# BIRDS-5_FM__Z_Panel_Ver2.net
KiCad netlist of a schematic drawn in EAGLE
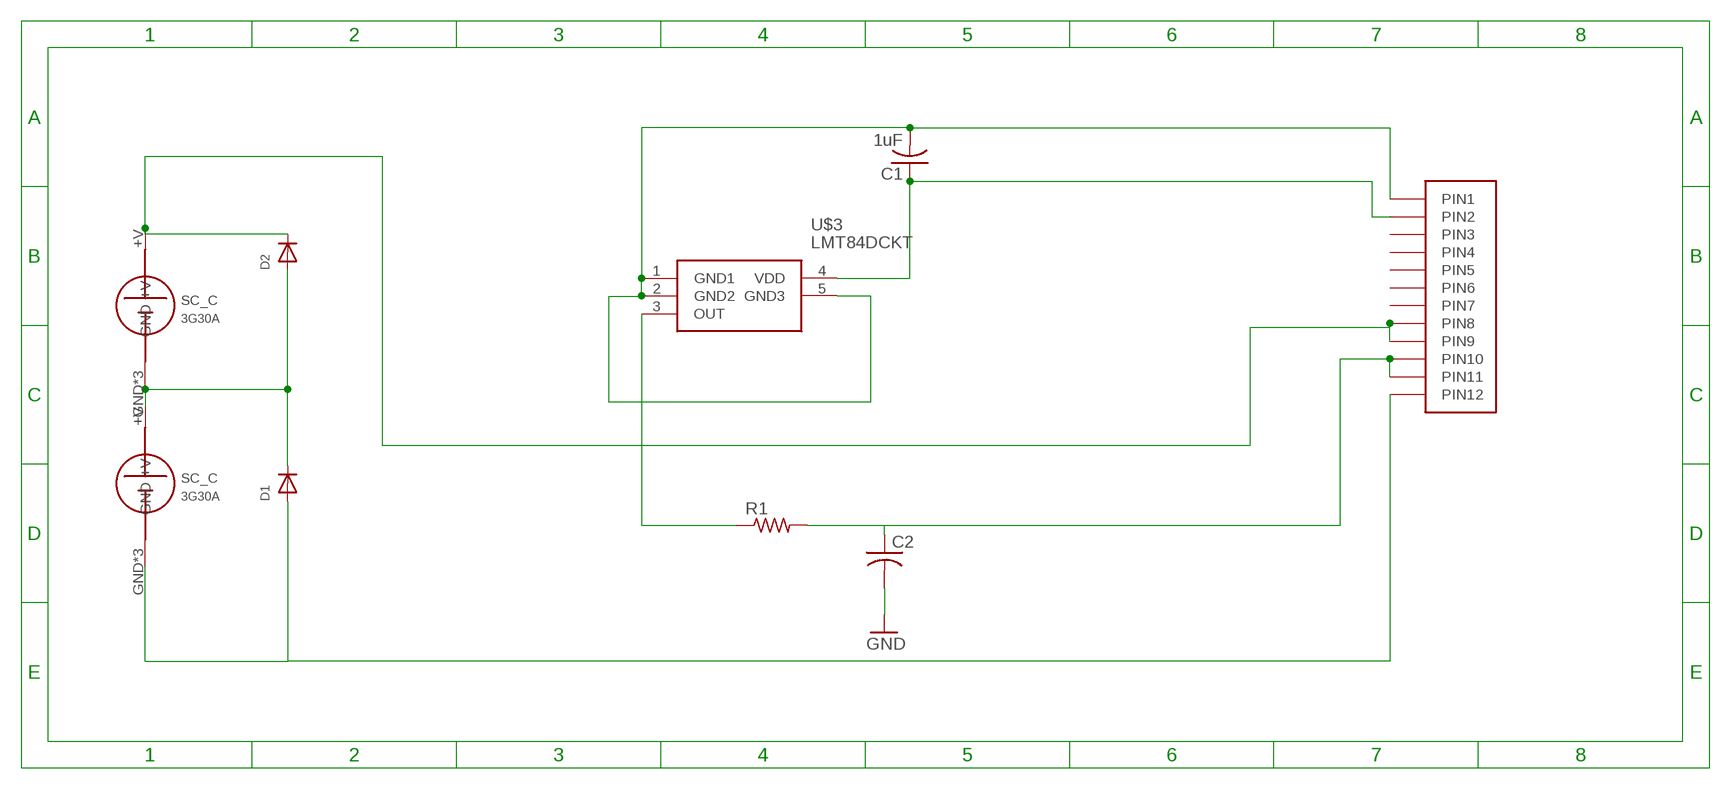
[diagram p0: schematic, sheet 1]

(export (version "E")
  (design (tool "Eeschema 10.0.6"))
  (components
    (comp (ref "C1")
      (value "1uF")
      (footprint "eagle-import:C2012")
      (libsource (lib "eagle-import") (part "C-USC2012"))
    )
    (comp (ref "C2")
      (value "C-USC2012")
      (footprint "eagle-import:C2012")
      (libsource (lib "eagle-import") (part "C-USC2012"))
    )
    (comp (ref "D1")
      (value "DIODE_SOD-123FL")
      (footprint "eagle-import:SOD-123FL")
      (libsource (lib "eagle-import") (part "DIODE_SOD-123FL"))
    )
    (comp (ref "D2")
      (value "DIODE_SOD-123FL")
      (footprint "eagle-import:SOD-123FL")
      (libsource (lib "eagle-import") (part "DIODE_SOD-123FL"))
    )
    (comp (ref "R1")
      (value "R-US_R0402")
      (footprint "eagle-import:R0402")
      (libsource (lib "eagle-import") (part "R-US_R0402"))
    )
    (comp (ref "U$1")
      (value "HEADER12PIN")
      (footprint "eagle-import:HEADER12PIN")
      (libsource (lib "eagle-import") (part "HEADER12PIN"))
    )
    (comp (ref "U$3")
      (value "LMT84DCKT")
      (footprint "eagle-import:SOT65P210X110-5N")
      (fields (field (name "RS_PART_NUMBER") "8115860"))
      (libsource (lib "eagle-import") (part "LMT84DCKT"))
    )
    (comp (ref "U$4")
      (value "SC_C")
      (footprint "eagle-import:SC_C")
      (libsource (lib "eagle-import") (part "SC_C"))
    )
    (comp (ref "U$5")
      (value "SC_C")
      (footprint "eagle-import:SC_C")
      (libsource (lib "eagle-import") (part "SC_C"))
    )
  )
  (nets
    (net (code "1") (name "GND") (class "Default")
      (node (ref "C1") (pin "2") (pinfunction "2_2") (pintype "passive"))
      (node (ref "C2") (pin "2") (pinfunction "2_2") (pintype "passive"))
      (node (ref "D1") (pin "A") (pinfunction "A_A") (pintype "passive"))
      (node (ref "U$1") (pin "P1") (pinfunction "PIN1_P1") (pintype "bidirectional"))
      (node (ref "U$1") (pin "P12") (pinfunction "PIN12_P12") (pintype "bidirectional"))
      (node (ref "U$3") (pin "1") (pinfunction "GND1_1") (pintype "power_in"))
      (node (ref "U$3") (pin "2") (pinfunction "GND2_2") (pintype "power_in"))
      (node (ref "U$3") (pin "5") (pinfunction "GND3_5") (pintype "power_in"))
      (node (ref "U$5") (pin "GND") (pinfunction "GND_GND") (pintype "bidirectional"))
      (node (ref "U$5") (pin "GND1") (pinfunction "GND_GND1") (pintype "bidirectional"))
      (node (ref "U$5") (pin "GND2") (pinfunction "GND_GND2") (pintype "bidirectional"))
    )
    (net (code "2") (name "Net-(D1-PadC)") (class "Default")
      (node (ref "D1") (pin "C") (pinfunction "C_C") (pintype "passive"))
      (node (ref "D2") (pin "A") (pinfunction "A_A") (pintype "passive"))
      (node (ref "U$4") (pin "GND") (pinfunction "GND_GND") (pintype "bidirectional"))
      (node (ref "U$4") (pin "GND1") (pinfunction "GND_GND1") (pintype "bidirectional"))
      (node (ref "U$4") (pin "GND2") (pinfunction "GND_GND2") (pintype "bidirectional"))
      (node (ref "U$5") (pin "+V") (pinfunction "+V_+V") (pintype "bidirectional"))
    )
    (net (code "3") (name "Net-(U$1-PIN2)") (class "Default")
      (node (ref "C1") (pin "1") (pinfunction "1_1") (pintype "passive"))
      (node (ref "U$1") (pin "P2") (pinfunction "PIN2_P2") (pintype "bidirectional"))
      (node (ref "U$3") (pin "4") (pinfunction "VDD_4") (pintype "power_in"))
    )
    (net (code "4") (name "Net-(U$1-PIN8)") (class "Default")
      (node (ref "D2") (pin "C") (pinfunction "C_C") (pintype "passive"))
      (node (ref "U$1") (pin "P8") (pinfunction "PIN8_P8") (pintype "bidirectional"))
      (node (ref "U$1") (pin "P9") (pinfunction "PIN9_P9") (pintype "bidirectional"))
      (node (ref "U$4") (pin "+V") (pinfunction "+V_+V") (pintype "bidirectional"))
    )
    (net (code "5") (name "Net-(U$1-PIN10)") (class "Default")
      (node (ref "C2") (pin "1") (pinfunction "1_1") (pintype "passive"))
      (node (ref "R1") (pin "2") (pinfunction "2_2") (pintype "passive"))
      (node (ref "U$1") (pin "P10") (pinfunction "PIN10_P10") (pintype "bidirectional"))
      (node (ref "U$1") (pin "P11") (pinfunction "PIN11_P11") (pintype "bidirectional"))
    )
    (net (code "6") (name "Net-(U$3-OUT)") (class "Default")
      (node (ref "R1") (pin "1") (pinfunction "1_1") (pintype "passive"))
      (node (ref "U$3") (pin "3") (pinfunction "OUT_3") (pintype "output"))
    )
    (net (code "7") (name "unconnected-(U$1-PIN3-PadP3)") (class "Default")
      (node (ref "U$1") (pin "P3") (pinfunction "PIN3_P3") (pintype "bidirectional"))
    )
    (net (code "8") (name "unconnected-(U$1-PIN4-PadP4)") (class "Default")
      (node (ref "U$1") (pin "P4") (pinfunction "PIN4_P4") (pintype "bidirectional"))
    )
    (net (code "9") (name "unconnected-(U$1-PIN5-PadP5)") (class "Default")
      (node (ref "U$1") (pin "P5") (pinfunction "PIN5_P5") (pintype "bidirectional"))
    )
    (net (code "10") (name "unconnected-(U$1-PIN6-PadP6)") (class "Default")
      (node (ref "U$1") (pin "P6") (pinfunction "PIN6_P6") (pintype "bidirectional"))
    )
    (net (code "11") (name "unconnected-(U$1-PIN7-PadP7)") (class "Default")
      (node (ref "U$1") (pin "P7") (pinfunction "PIN7_P7") (pintype "bidirectional"))
    )
  )
)
